# iv17-display-shield.net
KiCad netlist of a schematic drawn in EAGLE
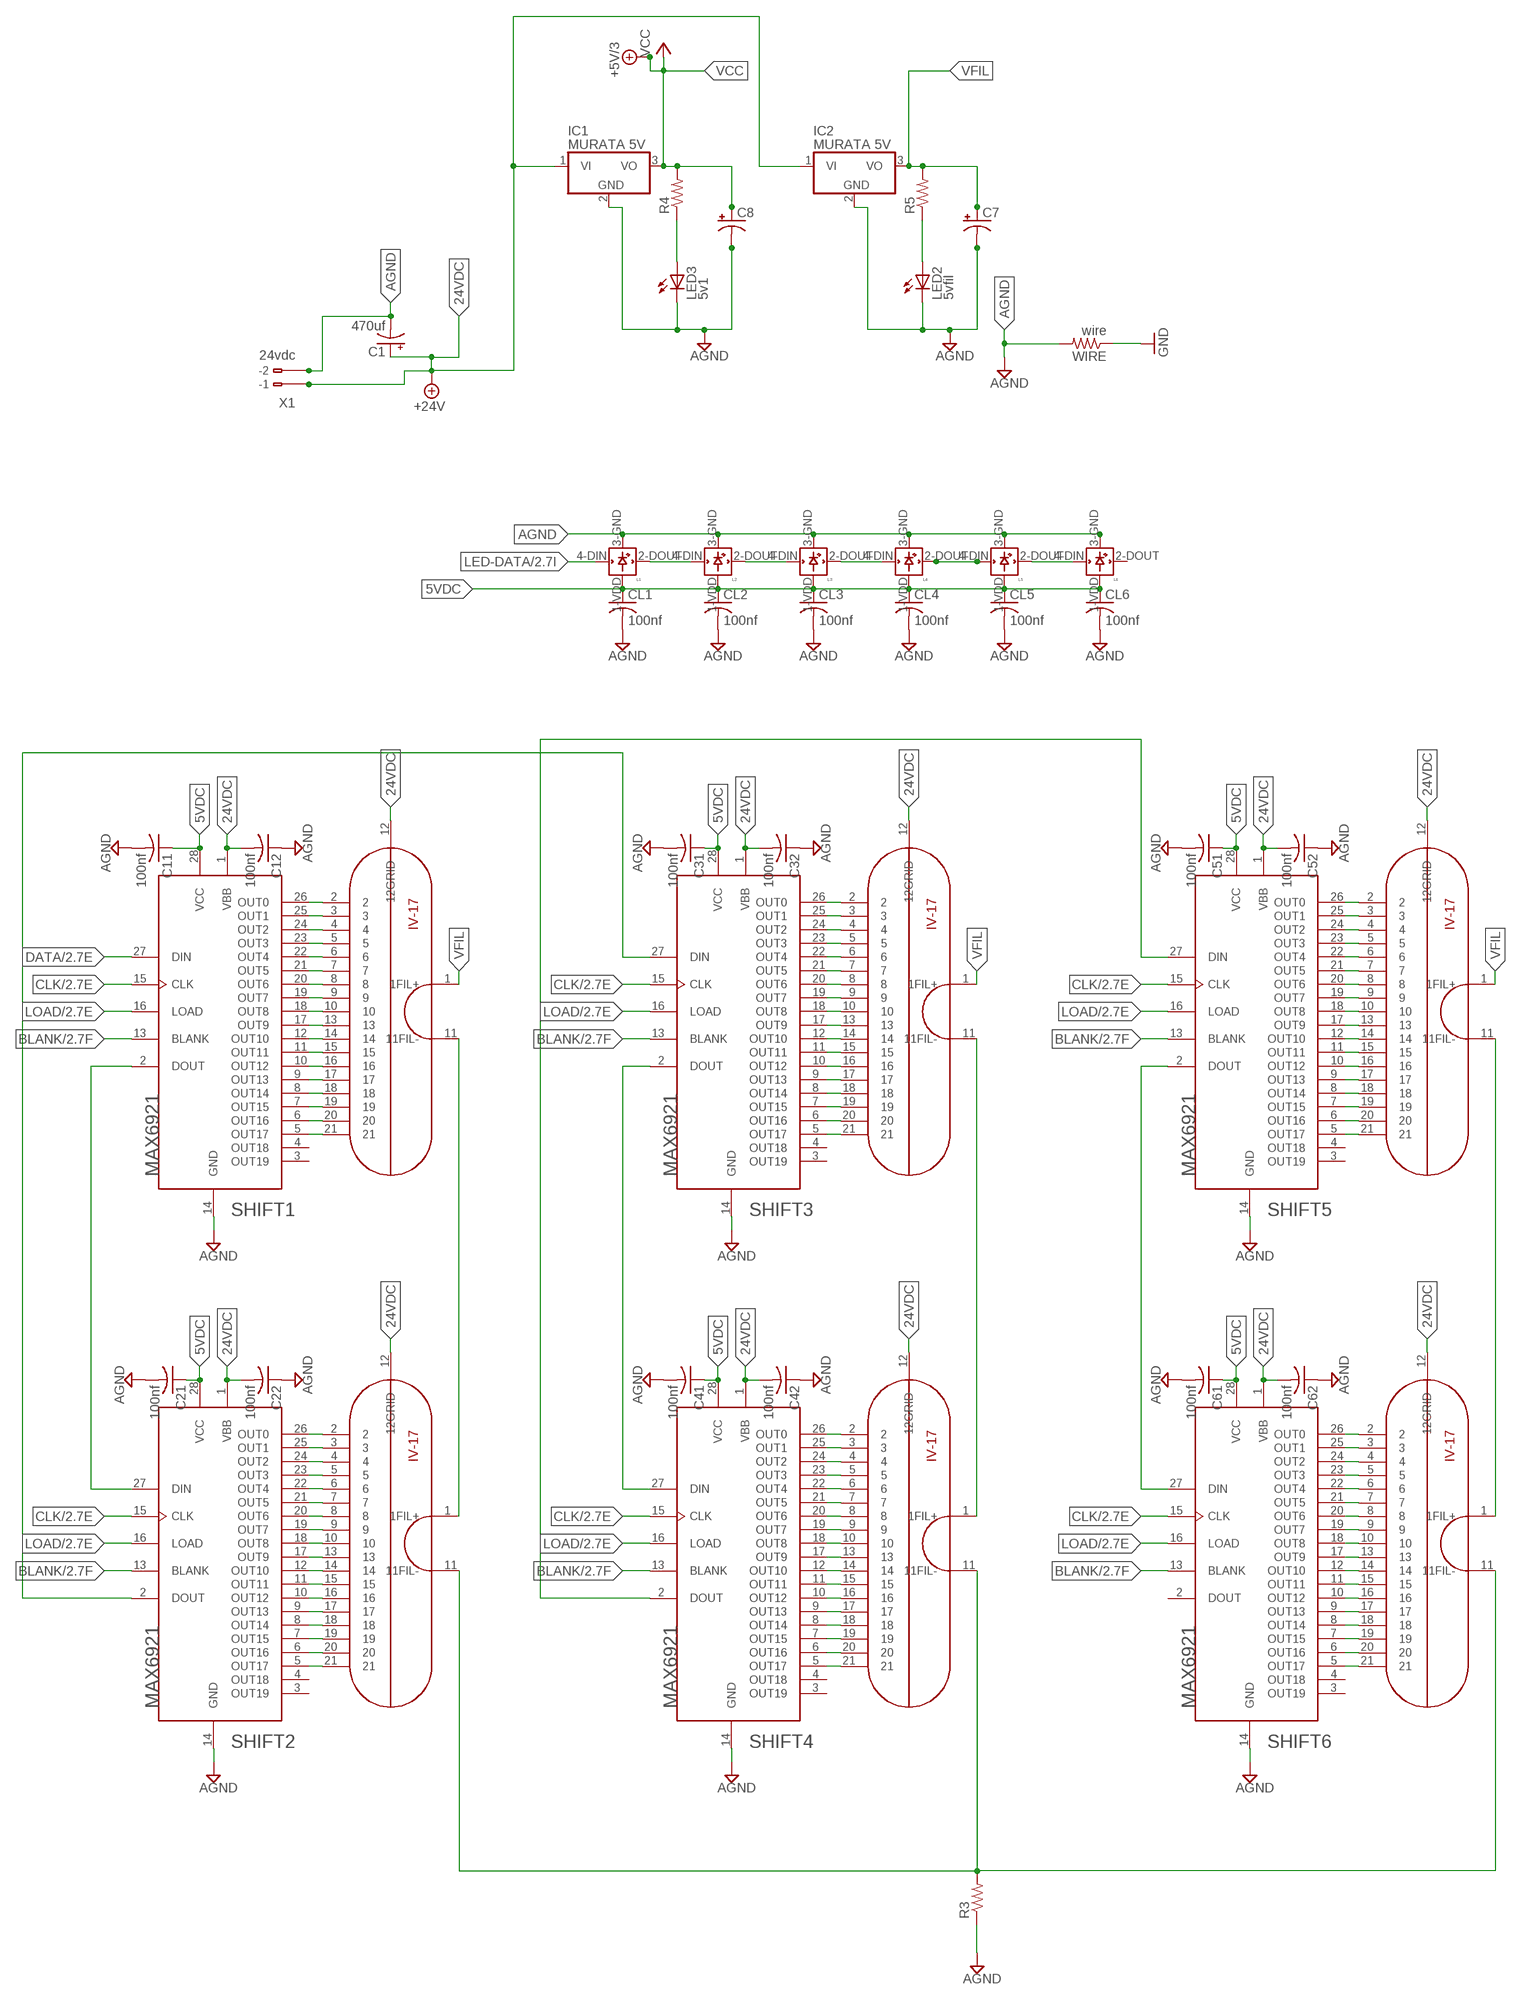
[diagram p0: schematic, sheet 1]
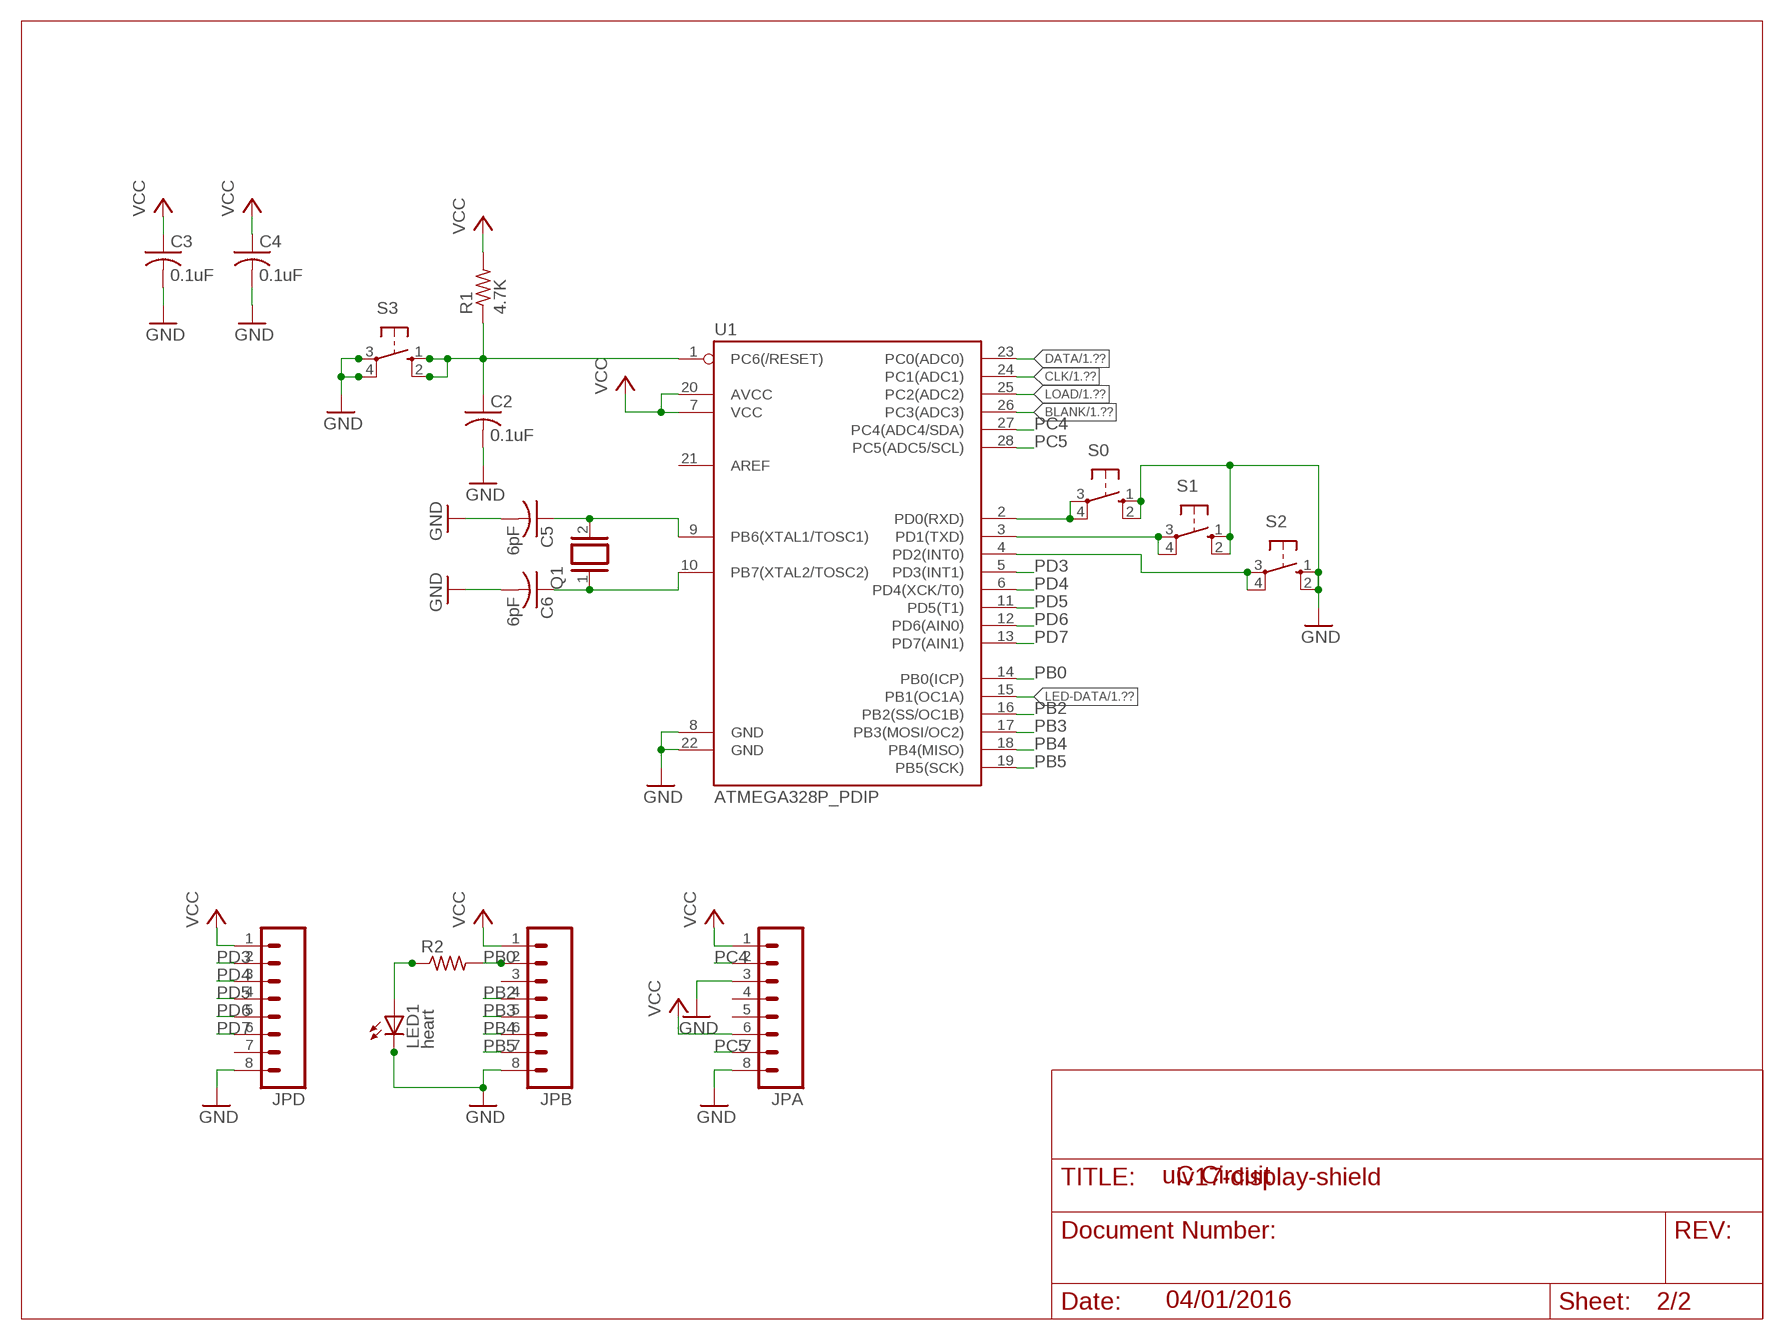
[diagram p1: schematic, sheet 2]

(export (version "E")
  (design (tool "Eeschema 10.0.6"))
  (components
    (comp (ref "C2")
      (value "0.1uF")
      (footprint "eagle-import:C1206")
      (libsource (lib "eagle-import") (part "C-USC1206"))
    )
    (comp (ref "C3")
      (value "0.1uF")
      (footprint "eagle-import:C1206")
      (libsource (lib "eagle-import") (part "C-USC1206"))
    )
    (comp (ref "C4")
      (value "0.1uF")
      (footprint "eagle-import:C1206")
      (libsource (lib "eagle-import") (part "C-USC1206"))
    )
    (comp (ref "C5")
      (value "6pF")
      (footprint "eagle-import:C1206")
      (libsource (lib "eagle-import") (part "C-USC1206"))
    )
    (comp (ref "C6")
      (value "6pF")
      (footprint "eagle-import:C1206")
      (libsource (lib "eagle-import") (part "C-USC1206"))
    )
    (comp (ref "JPA")
      (value "M08")
      (footprint "eagle-import:1X08_ROUND")
      (libsource (lib "eagle-import") (part "M08"))
    )
    (comp (ref "JPB")
      (value "M08")
      (footprint "eagle-import:1X08_ROUND")
      (libsource (lib "eagle-import") (part "M08"))
    )
    (comp (ref "JPD")
      (value "M08")
      (footprint "eagle-import:1X08_ROUND")
      (libsource (lib "eagle-import") (part "M08"))
    )
    (comp (ref "LED1")
      (value "heart")
      (footprint "eagle-import:LED3MM")
      (fields (field (name "MF") "VISHAY SEMICONDUCTOR"))
      (libsource (lib "eagle-import") (part "TLLG4400"))
    )
    (comp (ref "Q1")
      (value "XTAL/S")
      (footprint "eagle-import:QS")
      (libsource (lib "eagle-import") (part "XTAL/S"))
    )
    (comp (ref "R1")
      (value "4.7K")
      (footprint "eagle-import:0309_12")
      (libsource (lib "eagle-import") (part "R-US_0309/12"))
    )
    (comp (ref "R2")
      (value "R-US_M1206")
      (footprint "eagle-import:M1206")
      (libsource (lib "eagle-import") (part "resistor_R-US_M1206"))
    )
    (comp (ref "S0")
      (value "40-XX")
      (footprint "eagle-import:B3F-40XX")
      (fields (field (name "MF") "OMRON COMPONENTS USA") (field (name "MPN") "B3F-4000"))
      (libsource (lib "eagle-import") (part "40-XX"))
    )
    (comp (ref "S1")
      (value "40-XX")
      (footprint "eagle-import:B3F-40XX")
      (fields (field (name "MF") "OMRON COMPONENTS USA") (field (name "MPN") "B3F-4000"))
      (libsource (lib "eagle-import") (part "40-XX"))
    )
    (comp (ref "S2")
      (value "40-XX")
      (footprint "eagle-import:B3F-40XX")
      (fields (field (name "MF") "OMRON COMPONENTS USA") (field (name "MPN") "B3F-4000"))
      (libsource (lib "eagle-import") (part "40-XX"))
    )
    (comp (ref "S3")
      (value "10-XX")
      (footprint "eagle-import:B3F-10XX")
      (fields (field (name "MPN") "B3F-1000"))
      (libsource (lib "eagle-import") (part "10-XX"))
    )
    (comp (ref "U1")
      (value "ATMEGA328P_PDIP")
      (footprint "eagle-import:DIL28-3")
      (libsource (lib "eagle-import") (part "ATMEGA328P_PDIP"))
    )
    (comp (ref "C1")
      (value "470uf")
      (footprint "eagle-import:E5-10,5")
      (libsource (lib "eagle-import") (part "CPOL-USE5-10.5"))
    )
    (comp (ref "C7")
      (value "CPOL-USE5-13")
      (footprint "eagle-import:E5-13")
      (libsource (lib "eagle-import") (part "CPOL-USE5-13"))
    )
    (comp (ref "C8")
      (value "CPOL-USE5-13")
      (footprint "eagle-import:E5-13")
      (libsource (lib "eagle-import") (part "CPOL-USE5-13"))
    )
    (comp (ref "C11")
      (value "100nf")
      (footprint "eagle-import:C1206")
      (libsource (lib "eagle-import") (part "C-USC1206"))
    )
    (comp (ref "C12")
      (value "100nf")
      (footprint "eagle-import:C1206")
      (libsource (lib "eagle-import") (part "C-USC1206"))
    )
    (comp (ref "C21")
      (value "100nf")
      (footprint "eagle-import:C1206")
      (libsource (lib "eagle-import") (part "C-USC1206"))
    )
    (comp (ref "C22")
      (value "100nf")
      (footprint "eagle-import:C1206")
      (libsource (lib "eagle-import") (part "C-USC1206"))
    )
    (comp (ref "C31")
      (value "100nf")
      (footprint "eagle-import:C1206")
      (libsource (lib "eagle-import") (part "C-USC1206"))
    )
    (comp (ref "C32")
      (value "100nf")
      (footprint "eagle-import:C1206")
      (libsource (lib "eagle-import") (part "C-USC1206"))
    )
    (comp (ref "C41")
      (value "100nf")
      (footprint "eagle-import:C1206")
      (libsource (lib "eagle-import") (part "C-USC1206"))
    )
    (comp (ref "C42")
      (value "100nf")
      (footprint "eagle-import:C1206")
      (libsource (lib "eagle-import") (part "C-USC1206"))
    )
    (comp (ref "C51")
      (value "100nf")
      (footprint "eagle-import:C1206")
      (libsource (lib "eagle-import") (part "C-USC1206"))
    )
    (comp (ref "C52")
      (value "100nf")
      (footprint "eagle-import:C1206")
      (libsource (lib "eagle-import") (part "C-USC1206"))
    )
    (comp (ref "C61")
      (value "100nf")
      (footprint "eagle-import:C1206")
      (libsource (lib "eagle-import") (part "C-USC1206"))
    )
    (comp (ref "C62")
      (value "100nf")
      (footprint "eagle-import:C1206")
      (libsource (lib "eagle-import") (part "C-USC1206"))
    )
    (comp (ref "CL1")
      (value "100nf")
      (footprint "eagle-import:C1206")
      (libsource (lib "eagle-import") (part "C-USC1206"))
    )
    (comp (ref "CL2")
      (value "100nf")
      (footprint "eagle-import:C1206")
      (libsource (lib "eagle-import") (part "C-USC1206"))
    )
    (comp (ref "CL3")
      (value "100nf")
      (footprint "eagle-import:C1206")
      (libsource (lib "eagle-import") (part "C-USC1206"))
    )
    (comp (ref "CL4")
      (value "100nf")
      (footprint "eagle-import:C1206")
      (libsource (lib "eagle-import") (part "C-USC1206"))
    )
    (comp (ref "CL5")
      (value "100nf")
      (footprint "eagle-import:C1206")
      (libsource (lib "eagle-import") (part "C-USC1206"))
    )
    (comp (ref "CL6")
      (value "100nf")
      (footprint "eagle-import:C1206")
      (libsource (lib "eagle-import") (part "C-USC1206"))
    )
    (comp (ref "IC1")
      (value "MURATA 5V")
      (footprint "eagle-import:TO220V")
      (libsource (lib "eagle-import") (part "78TV6"))
    )
    (comp (ref "IC2")
      (value "MURATA 5V")
      (footprint "eagle-import:TO220V")
      (libsource (lib "eagle-import") (part "78TV6"))
    )
    (comp (ref "L1")
      (value "WS2812B")
      (footprint "eagle-import:WS2812B")
      (libsource (lib "eagle-import") (part "WS2812B"))
    )
    (comp (ref "L2")
      (value "WS2812B")
      (footprint "eagle-import:WS2812B")
      (libsource (lib "eagle-import") (part "WS2812B"))
    )
    (comp (ref "L3")
      (value "WS2812B")
      (footprint "eagle-import:WS2812B")
      (libsource (lib "eagle-import") (part "WS2812B"))
    )
    (comp (ref "L4")
      (value "WS2812B")
      (footprint "eagle-import:WS2812B")
      (libsource (lib "eagle-import") (part "WS2812B"))
    )
    (comp (ref "L5")
      (value "WS2812B")
      (footprint "eagle-import:WS2812B")
      (libsource (lib "eagle-import") (part "WS2812B"))
    )
    (comp (ref "L6")
      (value "WS2812B")
      (footprint "eagle-import:WS2812B")
      (libsource (lib "eagle-import") (part "WS2812B"))
    )
    (comp (ref "LED2")
      (value "5vfil")
      (footprint "eagle-import:LED3MM")
      (fields (field (name "MF") "VISHAY SEMICONDUCTOR"))
      (libsource (lib "eagle-import") (part "TLLR4400"))
    )
    (comp (ref "LED3")
      (value "5v1")
      (footprint "eagle-import:LED3MM")
      (fields (field (name "MF") "VISHAY SEMICONDUCTOR"))
      (libsource (lib "eagle-import") (part "TLLR4400"))
    )
    (comp (ref "R3")
      (value "R-US_0309/12")
      (footprint "eagle-import:0309_12")
      (libsource (lib "eagle-import") (part "R-US_0309/12"))
    )
    (comp (ref "R4")
      (value "R-US_M1206")
      (footprint "eagle-import:M1206")
      (libsource (lib "eagle-import") (part "resistor_R-US_M1206"))
    )
    (comp (ref "R5")
      (value "R-US_M1206")
      (footprint "eagle-import:M1206")
      (libsource (lib "eagle-import") (part "resistor_R-US_M1206"))
    )
    (comp (ref "SHIFT1")
      (value "MAX6921")
      (footprint "eagle-import:SOIC-28W")
      (libsource (lib "eagle-import") (part "MAX6921"))
    )
    (comp (ref "SHIFT2")
      (value "MAX6921")
      (footprint "eagle-import:SOIC-28W")
      (libsource (lib "eagle-import") (part "MAX6921"))
    )
    (comp (ref "SHIFT3")
      (value "MAX6921")
      (footprint "eagle-import:SOIC-28W")
      (libsource (lib "eagle-import") (part "MAX6921"))
    )
    (comp (ref "SHIFT4")
      (value "MAX6921")
      (footprint "eagle-import:SOIC-28W")
      (libsource (lib "eagle-import") (part "MAX6921"))
    )
    (comp (ref "SHIFT5")
      (value "MAX6921")
      (footprint "eagle-import:SOIC-28W")
      (libsource (lib "eagle-import") (part "MAX6921"))
    )
    (comp (ref "SHIFT6")
      (value "MAX6921")
      (footprint "eagle-import:SOIC-28W")
      (libsource (lib "eagle-import") (part "MAX6921"))
    )
    (comp (ref "TUBE1")
      (value "IV17")
      (footprint "eagle-import:NIXIE-22")
      (libsource (lib "eagle-import") (part "IV17"))
    )
    (comp (ref "TUBE2")
      (value "IV17")
      (footprint "eagle-import:NIXIE-22")
      (libsource (lib "eagle-import") (part "IV17"))
    )
    (comp (ref "TUBE3")
      (value "IV17")
      (footprint "eagle-import:NIXIE-22")
      (libsource (lib "eagle-import") (part "IV17"))
    )
    (comp (ref "TUBE4")
      (value "IV17")
      (footprint "eagle-import:NIXIE-22")
      (libsource (lib "eagle-import") (part "IV17"))
    )
    (comp (ref "TUBE5")
      (value "IV17")
      (footprint "eagle-import:NIXIE-22")
      (libsource (lib "eagle-import") (part "IV17"))
    )
    (comp (ref "TUBE6")
      (value "IV17")
      (footprint "eagle-import:NIXIE-22")
      (libsource (lib "eagle-import") (part "IV17"))
    )
    (comp (ref "WIRE")
      (value "wire")
      (footprint "eagle-import:0309_12")
      (libsource (lib "eagle-import") (part "R-US_0309/12"))
    )
    (comp (ref "X1")
      (value "24vdc")
      (footprint "eagle-import:233-102")
      (fields (field (name "MPN") "233-102"))
      (libsource (lib "eagle-import") (part "233-102"))
    )
  )
  (nets
    (net (code "1") (name "5VDC") (class "Default")
      (node (ref "C11") (pin "1") (pinfunction "1_1") (pintype "passive"))
      (node (ref "C21") (pin "1") (pinfunction "1_1") (pintype "passive"))
      (node (ref "C31") (pin "1") (pinfunction "1_1") (pintype "passive"))
      (node (ref "C41") (pin "1") (pinfunction "1_1") (pintype "passive"))
      (node (ref "C51") (pin "1") (pinfunction "1_1") (pintype "passive"))
      (node (ref "C61") (pin "1") (pinfunction "1_1") (pintype "passive"))
      (node (ref "CL1") (pin "1") (pinfunction "1_1") (pintype "passive"))
      (node (ref "CL2") (pin "1") (pinfunction "1_1") (pintype "passive"))
      (node (ref "CL3") (pin "1") (pinfunction "1_1") (pintype "passive"))
      (node (ref "CL4") (pin "1") (pinfunction "1_1") (pintype "passive"))
      (node (ref "CL5") (pin "1") (pinfunction "1_1") (pintype "passive"))
      (node (ref "CL6") (pin "1") (pinfunction "1_1") (pintype "passive"))
      (node (ref "L1") (pin "1-VDD") (pinfunction "VDD_1-VDD") (pintype "bidirectional"))
      (node (ref "L2") (pin "1-VDD") (pinfunction "VDD_1-VDD") (pintype "bidirectional"))
      (node (ref "L3") (pin "1-VDD") (pinfunction "VDD_1-VDD") (pintype "bidirectional"))
      (node (ref "L4") (pin "1-VDD") (pinfunction "VDD_1-VDD") (pintype "bidirectional"))
      (node (ref "L5") (pin "1-VDD") (pinfunction "VDD_1-VDD") (pintype "bidirectional"))
      (node (ref "L6") (pin "1-VDD") (pinfunction "VDD_1-VDD") (pintype "bidirectional"))
      (node (ref "SHIFT1") (pin "28") (pinfunction "VCC_28") (pintype "power_in"))
      (node (ref "SHIFT2") (pin "28") (pinfunction "VCC_28") (pintype "power_in"))
      (node (ref "SHIFT3") (pin "28") (pinfunction "VCC_28") (pintype "power_in"))
      (node (ref "SHIFT4") (pin "28") (pinfunction "VCC_28") (pintype "power_in"))
      (node (ref "SHIFT5") (pin "28") (pinfunction "VCC_28") (pintype "power_in"))
      (node (ref "SHIFT6") (pin "28") (pinfunction "VCC_28") (pintype "power_in"))
    )
    (net (code "2") (name "24VDC") (class "Default")
      (node (ref "C1") (pin "+") (pinfunction "+_+") (pintype "passive"))
      (node (ref "C12") (pin "2") (pinfunction "2_2") (pintype "passive"))
      (node (ref "C22") (pin "2") (pinfunction "2_2") (pintype "passive"))
      (node (ref "C32") (pin "2") (pinfunction "2_2") (pintype "passive"))
      (node (ref "C42") (pin "2") (pinfunction "2_2") (pintype "passive"))
      (node (ref "C52") (pin "2") (pinfunction "2_2") (pintype "passive"))
      (node (ref "C62") (pin "2") (pinfunction "2_2") (pintype "passive"))
      (node (ref "IC1") (pin "1") (pinfunction "VI_1") (pintype "input"))
      (node (ref "IC2") (pin "1") (pinfunction "VI_1") (pintype "input"))
      (node (ref "SHIFT1") (pin "1") (pinfunction "VBB_1") (pintype "power_in"))
      (node (ref "SHIFT2") (pin "1") (pinfunction "VBB_1") (pintype "power_in"))
      (node (ref "SHIFT3") (pin "1") (pinfunction "VBB_1") (pintype "power_in"))
      (node (ref "SHIFT4") (pin "1") (pinfunction "VBB_1") (pintype "power_in"))
      (node (ref "SHIFT5") (pin "1") (pinfunction "VBB_1") (pintype "power_in"))
      (node (ref "SHIFT6") (pin "1") (pinfunction "VBB_1") (pintype "power_in"))
      (node (ref "TUBE1") (pin "12") (pinfunction "12GRID_12") (pintype "bidirectional"))
      (node (ref "TUBE2") (pin "12") (pinfunction "12GRID_12") (pintype "bidirectional"))
      (node (ref "TUBE3") (pin "12") (pinfunction "12GRID_12") (pintype "bidirectional"))
      (node (ref "TUBE4") (pin "12") (pinfunction "12GRID_12") (pintype "bidirectional"))
      (node (ref "TUBE5") (pin "12") (pinfunction "12GRID_12") (pintype "bidirectional"))
      (node (ref "TUBE6") (pin "12") (pinfunction "12GRID_12") (pintype "bidirectional"))
      (node (ref "X1") (pin "B1") (pinfunction "B-1_B1") (pintype "passive"))
    )
    (net (code "3") (name "AGND") (class "Default")
      (node (ref "C1") (pin "-") (pinfunction "-_-") (pintype "passive"))
      (node (ref "C11") (pin "2") (pinfunction "2_2") (pintype "passive"))
      (node (ref "C12") (pin "1") (pinfunction "1_1") (pintype "passive"))
      (node (ref "C21") (pin "2") (pinfunction "2_2") (pintype "passive"))
      (node (ref "C22") (pin "1") (pinfunction "1_1") (pintype "passive"))
      (node (ref "C31") (pin "2") (pinfunction "2_2") (pintype "passive"))
      (node (ref "C32") (pin "1") (pinfunction "1_1") (pintype "passive"))
      (node (ref "C41") (pin "2") (pinfunction "2_2") (pintype "passive"))
      (node (ref "C42") (pin "1") (pinfunction "1_1") (pintype "passive"))
      (node (ref "C51") (pin "2") (pinfunction "2_2") (pintype "passive"))
      (node (ref "C52") (pin "1") (pinfunction "1_1") (pintype "passive"))
      (node (ref "C61") (pin "2") (pinfunction "2_2") (pintype "passive"))
      (node (ref "C62") (pin "1") (pinfunction "1_1") (pintype "passive"))
      (node (ref "C7") (pin "-") (pinfunction "-_-") (pintype "passive"))
      (node (ref "C8") (pin "-") (pinfunction "-_-") (pintype "passive"))
      (node (ref "CL1") (pin "2") (pinfunction "2_2") (pintype "passive"))
      (node (ref "CL2") (pin "2") (pinfunction "2_2") (pintype "passive"))
      (node (ref "CL3") (pin "2") (pinfunction "2_2") (pintype "passive"))
      (node (ref "CL4") (pin "2") (pinfunction "2_2") (pintype "passive"))
      (node (ref "CL5") (pin "2") (pinfunction "2_2") (pintype "passive"))
      (node (ref "CL6") (pin "2") (pinfunction "2_2") (pintype "passive"))
      (node (ref "IC1") (pin "2") (pinfunction "GND_2") (pintype "passive"))
      (node (ref "IC2") (pin "2") (pinfunction "GND_2") (pintype "passive"))
      (node (ref "L1") (pin "3-GND") (pinfunction "GND_3-GND") (pintype "bidirectional"))
      (node (ref "L2") (pin "3-GND") (pinfunction "GND_3-GND") (pintype "bidirectional"))
      (node (ref "L3") (pin "3-GND") (pinfunction "GND_3-GND") (pintype "bidirectional"))
      (node (ref "L4") (pin "3-GND") (pinfunction "GND_3-GND") (pintype "bidirectional"))
      (node (ref "L5") (pin "3-GND") (pinfunction "GND_3-GND") (pintype "bidirectional"))
      (node (ref "L6") (pin "3-GND") (pinfunction "GND_3-GND") (pintype "bidirectional"))
      (node (ref "LED2") (pin "K") (pinfunction "C_K") (pintype "passive"))
      (node (ref "LED3") (pin "K") (pinfunction "C_K") (pintype "passive"))
      (node (ref "R3") (pin "1") (pinfunction "1_1") (pintype "passive"))
      (node (ref "SHIFT1") (pin "14") (pinfunction "GND_14") (pintype "power_in"))
      (node (ref "SHIFT2") (pin "14") (pinfunction "GND_14") (pintype "power_in"))
      (node (ref "SHIFT3") (pin "14") (pinfunction "GND_14") (pintype "power_in"))
      (node (ref "SHIFT4") (pin "14") (pinfunction "GND_14") (pintype "power_in"))
      (node (ref "SHIFT5") (pin "14") (pinfunction "GND_14") (pintype "power_in"))
      (node (ref "SHIFT6") (pin "14") (pinfunction "GND_14") (pintype "power_in"))
      (node (ref "WIRE") (pin "2") (pinfunction "2_2") (pintype "passive"))
      (node (ref "X1") (pin "B2") (pinfunction "B-2_B2") (pintype "passive"))
    )
    (net (code "4") (name "BLANK") (class "Default")
      (node (ref "SHIFT1") (pin "13") (pinfunction "BLANK_13") (pintype "input"))
      (node (ref "SHIFT2") (pin "13") (pinfunction "BLANK_13") (pintype "input"))
      (node (ref "SHIFT3") (pin "13") (pinfunction "BLANK_13") (pintype "input"))
      (node (ref "SHIFT4") (pin "13") (pinfunction "BLANK_13") (pintype "input"))
      (node (ref "SHIFT5") (pin "13") (pinfunction "BLANK_13") (pintype "input"))
      (node (ref "SHIFT6") (pin "13") (pinfunction "BLANK_13") (pintype "input"))
      (node (ref "U1") (pin "26") (pinfunction "PC3(ADC3)_26") (pintype "bidirectional"))
    )
    (net (code "5") (name "CLK") (class "Default")
      (node (ref "SHIFT1") (pin "15") (pinfunction "CLK_15") (pintype "input"))
      (node (ref "SHIFT2") (pin "15") (pinfunction "CLK_15") (pintype "input"))
      (node (ref "SHIFT3") (pin "15") (pinfunction "CLK_15") (pintype "input"))
      (node (ref "SHIFT4") (pin "15") (pinfunction "CLK_15") (pintype "input"))
      (node (ref "SHIFT5") (pin "15") (pinfunction "CLK_15") (pintype "input"))
      (node (ref "SHIFT6") (pin "15") (pinfunction "CLK_15") (pintype "input"))
      (node (ref "U1") (pin "24") (pinfunction "PC1(ADC1)_24") (pintype "bidirectional"))
    )
    (net (code "6") (name "DATA") (class "Default")
      (node (ref "SHIFT1") (pin "27") (pinfunction "DIN_27") (pintype "input"))
      (node (ref "U1") (pin "23") (pinfunction "PC0(ADC0)_23") (pintype "bidirectional"))
    )
    (net (code "7") (name "GND") (class "Default")
      (node (ref "C2") (pin "2") (pinfunction "2_2") (pintype "passive"))
      (node (ref "C3") (pin "2") (pinfunction "2_2") (pintype "passive"))
      (node (ref "C4") (pin "2") (pinfunction "2_2") (pintype "passive"))
      (node (ref "C5") (pin "2") (pinfunction "2_2") (pintype "passive"))
      (node (ref "C6") (pin "2") (pinfunction "2_2") (pintype "passive"))
      (node (ref "JPA") (pin "3") (pinfunction "3_3") (pintype "passive"))
      (node (ref "JPA") (pin "8") (pinfunction "8_8") (pintype "passive"))
      (node (ref "JPB") (pin "8") (pinfunction "8_8") (pintype "passive"))
      (node (ref "JPD") (pin "8") (pinfunction "8_8") (pintype "passive"))
      (node (ref "LED1") (pin "K") (pinfunction "C_K") (pintype "passive"))
      (node (ref "S0") (pin "1") (pinfunction "S_1") (pintype "passive"))
      (node (ref "S0") (pin "2") (pinfunction "S1_2") (pintype "passive"))
      (node (ref "S1") (pin "1") (pinfunction "S_1") (pintype "passive"))
      (node (ref "S1") (pin "2") (pinfunction "S1_2") (pintype "passive"))
      (node (ref "S2") (pin "1") (pinfunction "S_1") (pintype "passive"))
      (node (ref "S2") (pin "2") (pinfunction "S1_2") (pintype "passive"))
      (node (ref "S3") (pin "3") (pinfunction "P_3") (pintype "passive"))
      (node (ref "S3") (pin "4") (pinfunction "P1_4") (pintype "passive"))
      (node (ref "U1") (pin "22") (pinfunction "GND_22") (pintype "bidirectional"))
      (node (ref "U1") (pin "8") (pinfunction "GND_8") (pintype "bidirectional"))
      (node (ref "WIRE") (pin "1") (pinfunction "1_1") (pintype "passive"))
    )
    (net (code "8") (name "LED-DATA") (class "Default")
      (node (ref "L1") (pin "4-DIN") (pinfunction "DIN_4-DIN") (pintype "input"))
      (node (ref "U1") (pin "15") (pinfunction "PB1(OC1A)_15") (pintype "bidirectional"))
    )
    (net (code "9") (name "LOAD") (class "Default")
      (node (ref "SHIFT1") (pin "16") (pinfunction "LOAD_16") (pintype "input"))
      (node (ref "SHIFT2") (pin "16") (pinfunction "LOAD_16") (pintype "input"))
      (node (ref "SHIFT3") (pin "16") (pinfunction "LOAD_16") (pintype "input"))
      (node (ref "SHIFT4") (pin "16") (pinfunction "LOAD_16") (pintype "input"))
      (node (ref "SHIFT5") (pin "16") (pinfunction "LOAD_16") (pintype "input"))
      (node (ref "SHIFT6") (pin "16") (pinfunction "LOAD_16") (pintype "input"))
      (node (ref "U1") (pin "25") (pinfunction "PC2(ADC2)_25") (pintype "bidirectional"))
    )
    (net (code "10") (name "Net-(L1-DOUT)") (class "Default")
      (node (ref "L1") (pin "2-DOUT") (pinfunction "DOUT_2-DOUT") (pintype "output"))
      (node (ref "L2") (pin "4-DIN") (pinfunction "DIN_4-DIN") (pintype "input"))
    )
    (net (code "11") (name "Net-(L2-DOUT)") (class "Default")
      (node (ref "L2") (pin "2-DOUT") (pinfunction "DOUT_2-DOUT") (pintype "output"))
      (node (ref "L3") (pin "4-DIN") (pinfunction "DIN_4-DIN") (pintype "input"))
    )
    (net (code "12") (name "Net-(L3-DOUT)") (class "Default")
      (node (ref "L3") (pin "2-DOUT") (pinfunction "DOUT_2-DOUT") (pintype "output"))
      (node (ref "L4") (pin "4-DIN") (pinfunction "DIN_4-DIN") (pintype "input"))
    )
    (net (code "13") (name "Net-(L4-DOUT)") (class "Default")
      (node (ref "L4") (pin "2-DOUT") (pinfunction "DOUT_2-DOUT") (pintype "output"))
      (node (ref "L5") (pin "4-DIN") (pinfunction "DIN_4-DIN") (pintype "input"))
    )
    (net (code "14") (name "Net-(L5-DOUT)") (class "Default")
      (node (ref "L5") (pin "2-DOUT") (pinfunction "DOUT_2-DOUT") (pintype "output"))
      (node (ref "L6") (pin "4-DIN") (pinfunction "DIN_4-DIN") (pintype "input"))
    )
    (net (code "15") (name "Net-(LED1-PadA)") (class "Default")
      (node (ref "LED1") (pin "A") (pinfunction "A_A") (pintype "passive"))
      (node (ref "R2") (pin "1") (pinfunction "1_1") (pintype "passive"))
    )
    (net (code "16") (name "Net-(LED2-PadA)") (class "Default")
      (node (ref "LED2") (pin "A") (pinfunction "A_A") (pintype "passive"))
      (node (ref "R5") (pin "1") (pinfunction "1_1") (pintype "passive"))
    )
    (net (code "17") (name "Net-(LED3-PadA)") (class "Default")
      (node (ref "LED3") (pin "A") (pinfunction "A_A") (pintype "passive"))
      (node (ref "R4") (pin "1") (pinfunction "1_1") (pintype "passive"))
    )
    (net (code "18") (name "Net-(S0-P)") (class "Default")
      (node (ref "S0") (pin "3") (pinfunction "P_3") (pintype "passive"))
      (node (ref "S0") (pin "4") (pinfunction "P1_4") (pintype "passive"))
      (node (ref "U1") (pin "2") (pinfunction "PD0(RXD)_2") (pintype "bidirectional"))
    )
    (net (code "19") (name "Net-(S1-P)") (class "Default")
      (node (ref "S1") (pin "3") (pinfunction "P_3") (pintype "passive"))
      (node (ref "S1") (pin "4") (pinfunction "P1_4") (pintype "passive"))
      (node (ref "U1") (pin "3") (pinfunction "PD1(TXD)_3") (pintype "bidirectional"))
    )
    (net (code "20") (name "Net-(S2-P)") (class "Default")
      (node (ref "S2") (pin "3") (pinfunction "P_3") (pintype "passive"))
      (node (ref "S2") (pin "4") (pinfunction "P1_4") (pintype "passive"))
      (node (ref "U1") (pin "4") (pinfunction "PD2(INT0)_4") (pintype "bidirectional"))
    )
    (net (code "21") (name "Net-(S3-S)") (class "Default")
      (node (ref "C2") (pin "1") (pinfunction "1_1") (pintype "passive"))
      (node (ref "R1") (pin "1") (pinfunction "1_1") (pintype "passive"))
      (node (ref "S3") (pin "1") (pinfunction "S_1") (pintype "passive"))
      (node (ref "S3") (pin "2") (pinfunction "S1_2") (pintype "passive"))
      (node (ref "U1") (pin "1") (pinfunction "PC6(/RESET)_1") (pintype "bidirectional"))
    )
    (net (code "22") (name "Net-(SHIFT1-DOUT)") (class "Default")
      (node (ref "SHIFT1") (pin "2") (pinfunction "DOUT_2") (pintype "output"))
      (node (ref "SHIFT2") (pin "27") (pinfunction "DIN_27") (pintype "input"))
    )
    (net (code "23") (name "Net-(SHIFT1-OUT0)") (class "Default")
      (node (ref "SHIFT1") (pin "26") (pinfunction "OUT0_26") (pintype "output"))
      (node (ref "TUBE1") (pin "2") (pinfunction "2_2") (pintype "bidirectional"))
    )
    (net (code "24") (name "Net-(SHIFT1-OUT1)") (class "Default")
      (node (ref "SHIFT1") (pin "25") (pinfunction "OUT1_25") (pintype "output"))
      (node (ref "TUBE1") (pin "3") (pinfunction "3_3") (pintype "bidirectional"))
    )
    (net (code "25") (name "Net-(SHIFT1-OUT2)") (class "Default")
      (node (ref "SHIFT1") (pin "24") (pinfunction "OUT2_24") (pintype "output"))
      (node (ref "TUBE1") (pin "4") (pinfunction "4_4") (pintype "bidirectional"))
    )
    (net (code "26") (name "Net-(SHIFT1-OUT3)") (class "Default")
      (node (ref "SHIFT1") (pin "23") (pinfunction "OUT3_23") (pintype "output"))
      (node (ref "TUBE1") (pin "5") (pinfunction "5_5") (pintype "bidirectional"))
    )
    (net (code "27") (name "Net-(SHIFT1-OUT4)") (class "Default")
      (node (ref "SHIFT1") (pin "22") (pinfunction "OUT4_22") (pintype "output"))
      (node (ref "TUBE1") (pin "6") (pinfunction "6_6") (pintype "bidirectional"))
    )
    (net (code "28") (name "Net-(SHIFT1-OUT5)") (class "Default")
      (node (ref "SHIFT1") (pin "21") (pinfunction "OUT5_21") (pintype "output"))
      (node (ref "TUBE1") (pin "7") (pinfunction "7_7") (pintype "bidirectional"))
    )
    (net (code "29") (name "Net-(SHIFT1-OUT6)") (class "Default")
      (node (ref "SHIFT1") (pin "20") (pinfunction "OUT6_20") (pintype "output"))
      (node (ref "TUBE1") (pin "8") (pinfunction "8_8") (pintype "bidirectional"))
    )
    (net (code "30") (name "Net-(SHIFT1-OUT7)") (class "Default")
      (node (ref "SHIFT1") (pin "19") (pinfunction "OUT7_19") (pintype "output"))
      (node (ref "TUBE1") (pin "9") (pinfunction "9_9") (pintype "bidirectional"))
    )
    (net (code "31") (name "Net-(SHIFT1-OUT8)") (class "Default")
      (node (ref "SHIFT1") (pin "18") (pinfunction "OUT8_18") (pintype "output"))
      (node (ref "TUBE1") (pin "10") (pinfunction "10_10") (pintype "bidirectional"))
    )
    (net (code "32") (name "Net-(SHIFT1-OUT9)") (class "Default")
      (node (ref "SHIFT1") (pin "17") (pinfunction "OUT9_17") (pintype "output"))
      (node (ref "TUBE1") (pin "13") (pinfunction "13_13") (pintype "bidirectional"))
    )
    (net (code "33") (name "Net-(SHIFT1-OUT10)") (class "Default")
      (node (ref "SHIFT1") (pin "12") (pinfunction "OUT10_12") (pintype "output"))
      (node (ref "TUBE1") (pin "14") (pinfunction "14_14") (pintype "bidirectional"))
    )
    (net (code "34") (name "Net-(SHIFT1-OUT11)") (class "Default")
      (node (ref "SHIFT1") (pin "11") (pinfunction "OUT11_11") (pintype "output"))
      (node (ref "TUBE1") (pin "15") (pinfunction "15_15") (pintype "bidirectional"))
    )
    (net (code "35") (name "Net-(SHIFT1-OUT12)") (class "Default")
      (node (ref "SHIFT1") (pin "10") (pinfunction "OUT12_10") (pintype "output"))
      (node (ref "TUBE1") (pin "16") (pinfunction "16_16") (pintype "bidirectional"))
    )
    (net (code "36") (name "Net-(SHIFT1-OUT13)") (class "Default")
      (node (ref "SHIFT1") (pin "9") (pinfunction "OUT13_9") (pintype "output"))
      (node (ref "TUBE1") (pin "17") (pinfunction "17_17") (pintype "bidirectional"))
    )
    (net (code "37") (name "Net-(SHIFT1-OUT14)") (class "Default")
      (node (ref "SHIFT1") (pin "8") (pinfunction "OUT14_8") (pintype "output"))
      (node (ref "TUBE1") (pin "18") (pinfunction "18_18") (pintype "bidirectional"))
    )
    (net (code "38") (name "Net-(SHIFT1-OUT15)") (class "Default")
      (node (ref "SHIFT1") (pin "7") (pinfunction "OUT15_7") (pintype "output"))
      (node (ref "TUBE1") (pin "19") (pinfunction "19_19") (pintype "bidirectional"))
    )
    (net (code "39") (name "Net-(SHIFT1-OUT16)") (class "Default")
      (node (ref "SHIFT1") (pin "6") (pinfunction "OUT16_6") (pintype "output"))
      (node (ref "TUBE1") (pin "20") (pinfunction "20_20") (pintype "bidirectional"))
    )
    (net (code "40") (name "Net-(SHIFT1-OUT17)") (class "Default")
      (node (ref "SHIFT1") (pin "5") (pinfunction "OUT17_5") (pintype "output"))
      (node (ref "TUBE1") (pin "21") (pinfunction "21_21") (pintype "bidirectional"))
    )
    (net (code "41") (name "Net-(SHIFT2-DOUT)") (class "Default")
      (node (ref "SHIFT2") (pin "2") (pinfunction "DOUT_2") (pintype "output"))
      (node (ref "SHIFT3") (pin "27") (pinfunction "DIN_27") (pintype "input"))
    )
    (net (code "42") (name "Net-(SHIFT2-OUT0)") (class "Default")
      (node (ref "SHIFT2") (pin "26") (pinfunction "OUT0_26") (pintype "output"))
      (node (ref "TUBE2") (pin "2") (pinfunction "2_2") (pintype "bidirectional"))
    )
    (net (code "43") (name "Net-(SHIFT2-OUT1)") (class "Default")
      (node (ref "SHIFT2") (pin "25") (pinfunction "OUT1_25") (pintype "output"))
      (node (ref "TUBE2") (pin "3") (pinfunction "3_3") (pintype "bidirectional"))
    )
    (net (code "44") (name "Net-(SHIFT2-OUT2)") (class "Default")
      (node (ref "SHIFT2") (pin "24") (pinfunction "OUT2_24") (pintype "output"))
      (node (ref "TUBE2") (pin "4") (pinfunction "4_4") (pintype "bidirectional"))
    )
    (net (code "45") (name "Net-(SHIFT2-OUT3)") (class "Default")
      (node (ref "SHIFT2") (pin "23") (pinfunction "OUT3_23") (pintype "output"))
      (node (ref "TUBE2") (pin "5") (pinfunction "5_5") (pintype "bidirectional"))
    )
    (net (code "46") (name "Net-(SHIFT2-OUT4)") (class "Default")
      (node (ref "SHIFT2") (pin "22") (pinfunction "OUT4_22") (pintype "output"))
      (node (ref "TUBE2") (pin "6") (pinfunction "6_6") (pintype "bidirectional"))
    )
    (net (code "47") (name "Net-(SHIFT2-OUT5)") (class "Default")
      (node (ref "SHIFT2") (pin "21") (pinfunction "OUT5_21") (pintype "output"))
      (node (ref "TUBE2") (pin "7") (pinfunction "7_7") (pintype "bidirectional"))
    )
    (net (code "48") (name "Net-(SHIFT2-OUT6)") (class "Default")
      (node (ref "SHIFT2") (pin "20") (pinfunction "OUT6_20") (pintype "output"))
      (node (ref "TUBE2") (pin "8") (pinfunction "8_8") (pintype "bidirectional"))
    )
    (net (code "49") (name "Net-(SHIFT2-OUT7)") (class "Default")
      (node (ref "SHIFT2") (pin "19") (pinfunction "OUT7_19") (pintype "output"))
      (node (ref "TUBE2") (pin "9") (pinfunction "9_9") (pintype "bidirectional"))
    )
    (net (code "50") (name "Net-(SHIFT2-OUT8)") (class "Default")
      (node (ref "SHIFT2") (pin "18") (pinfunction "OUT8_18") (pintype "output"))
      (node (ref "TUBE2") (pin "10") (pinfunction "10_10") (pintype "bidirectional"))
    )
    (net (code "51") (name "Net-(SHIFT2-OUT9)") (class "Default")
      (node (ref "SHIFT2") (pin "17") (pinfunction "OUT9_17") (pintype "output"))
      (node (ref "TUBE2") (pin "13") (pinfunction "13_13") (pintype "bidirectional"))
    )
    (net (code "52") (name "Net-(SHIFT2-OUT10)") (class "Default")
      (node (ref "SHIFT2") (pin "12") (pinfunction "OUT10_12") (pintype "output"))
      (node (ref "TUBE2") (pin "14") (pinfunction "14_14") (pintype "bidirectional"))
    )
    (net (code "53") (name "Net-(SHIFT2-OUT11)") (class "Default")
      (node (ref "SHIFT2") (pin "11") (pinfunction "OUT11_11") (pintype "output"))
      (node (ref "TUBE2") (pin "15") (pinfunction "15_15") (pintype "bidirectional"))
    )
    (net (code "54") (name "Net-(SHIFT2-OUT12)") (class "Default")
      (node (ref "SHIFT2") (pin "10") (pinfunction "OUT12_10") (pintype "output"))
      (node (ref "TUBE2") (pin "16") (pinfunction "16_16") (pintype "bidirectional"))
    )
    (net (code "55") (name "Net-(SHIFT2-OUT13)") (class "Default")
      (node (ref "SHIFT2") (pin "9") (pinfunction "OUT13_9") (pintype "output"))
      (node (ref "TUBE2") (pin "17") (pinfunction "17_17") (pintype "bidirectional"))
    )
    (net (code "56") (name "Net-(SHIFT2-OUT14)") (class "Default")
      (node (ref "SHIFT2") (pin "8") (pinfunction "OUT14_8") (pintype "output"))
      (node (ref "TUBE2") (pin "18") (pinfunction "18_18") (pintype "bidirectional"))
    )
    (net (code "57") (name "Net-(SHIFT2-OUT15)") (class "Default")
      (node (ref "SHIFT2") (pin "7") (pinfunction "OUT15_7") (pintype "output"))
      (node (ref "TUBE2") (pin "19") (pinfunction "19_19") (pintype "bidirectional"))
    )
    (net (code "58") (name "Net-(SHIFT2-OUT16)") (class "Default")
      (node (ref "SHIFT2") (pin "6") (pinfunction "OUT16_6") (pintype "output"))
      (node (ref "TUBE2") (pin "20") (pinfunction "20_20") (pintype "bidirectional"))
    )
    (net (code "59") (name "Net-(SHIFT2-OUT17)") (class "Default")
      (node (ref "SHIFT2") (pin "5") (pinfunction "OUT17_5") (pintype "output"))
      (node (ref "TUBE2") (pin "21") (pinfunction "21_21") (pintype "bidirectional"))
    )
    (net (code "60") (name "Net-(SHIFT3-DOUT)") (class "Default")
      (node (ref "SHIFT3") (pin "2") (pinfunction "DOUT_2") (pintype "output"))
      (node (ref "SHIFT4") (pin "27") (pinfunction "DIN_27") (pintype "input"))
    )
    (net (code "61") (name "Net-(SHIFT3-OUT0)") (class "Default")
      (node (ref "SHIFT3") (pin "26") (pinfunction "OUT0_26") (pintype "output"))
      (node (ref "TUBE3") (pin "2") (pinfunction "2_2") (pintype "bidirectional"))
    )
    (net (code "62") (name "Net-(SHIFT3-OUT1)") (class "Default")
      (node (ref "SHIFT3") (pin "25") (pinfunction "OUT1_25") (pintype "output"))
      (node (ref "TUBE3") (pin "3") (pinfunction "3_3") (pintype "bidirectional"))
    )
    (net (code "63") (name "Net-(SHIFT3-OUT2)") (class "Default")
      (node (ref "SHIFT3") (pin "24") (pinfunction "OUT2_24") (pintype "output"))
      (node (ref "TUBE3") (pin "4") (pinfunction "4_4") (pintype "bidirectional"))
    )
    (net (code "64") (name "Net-(SHIFT3-OUT3)") (class "Default")
      (node (ref "SHIFT3") (pin "23") (pinfunction "OUT3_23") (pintype "output"))
      (node (ref "TUBE3") (pin "5") (pinfunction "5_5") (pintype "bidirectional"))
    )
    (net (code "65") (name "Net-(SHIFT3-OUT4)") (class "Default")
      (node (ref "SHIFT3") (pin "22") (pinfunction "OUT4_22") (pintype "output"))
      (node (ref "TUBE3") (pin "6") (pinfunction "6_6") (pintype "bidirectional"))
    )
    (net (code "66") (name "Net-(SHIFT3-OUT5)") (class "Default")
      (node (ref "SHIFT3") (pin "21") (pinfunction "OUT5_21") (pintype "output"))
      (node (ref "TUBE3") (pin "7") (pinfunction "7_7") (pintype "bidirectional"))
    )
    (net (code "67") (name "Net-(SHIFT3-OUT6)") (class "Default")
      (node (ref "SHIFT3") (pin "20") (pinfunction "OUT6_20") (pintype "output"))
      (node (ref "TUBE3") (pin "8") (pinfunction "8_8") (pintype "bidirectional"))
    )
    (net (code "68") (name "Net-(SHIFT3-OUT7)") (class "Default")
      (node (ref "SHIFT3") (pin "19") (pinfunction "OUT7_19") (pintype "output"))
      (node (ref "TUBE3") (pin "9") (pinfunction "9_9") (pintype "bidirectional"))
    )
    (net (code "69") (name "Net-(SHIFT3-OUT8)") (class "Default")
      (node (ref "SHIFT3") (pin "18") (pinfunction "OUT8_18") (pintype "output"))
      (node (ref "TUBE3") (pin "10") (pinfunction "10_10") (pintype "bidirectional"))
    )
    (net (code "70") (name "Net-(SHIFT3-OUT9)") (class "Default")
      (node (ref "SHIFT3") (pin "17") (pinfunction "OUT9_17") (pintype "output"))
      (node (ref "TUBE3") (pin "13") (pinfunction "13_13") (pintype "bidirectional"))
    )
    (net (code "71") (name "Net-(SHIFT3-OUT10)") (class "Default")
      (node (ref "SHIFT3") (pin "12") (pinfunction "OUT10_12") (pintype "output"))
      (node (ref "TUBE3") (pin "14") (pinfunction "14_14") (pintype "bidirectional"))
    )
    (net (code "72") (name "Net-(SHIFT3-OUT11)") (class "Default")
      (node (ref "SHIFT3") (pin "11") (pinfunction "OUT11_11") (pintype "output"))
      (node (ref "TUBE3") (pin "15") (pinfunction "15_15") (pintype "bidirectional"))
    )
    (net (code "73") (name "Net-(SHIFT3-OUT12)") (class "Default")
      (node (ref "SHIFT3") (pin "10") (pinfunction "OUT12_10") (pintype "output"))
      (node (ref "TUBE3") (pin "16") (pinfunction "16_16") (pintype "bidirectional"))
    )
    (net (code "74") (name "Net-(SHIFT3-OUT13)") (class "Default")
      (node (ref "SHIFT3") (pin "9") (pinfunction "OUT13_9") (pintype "output"))
      (node (ref "TUBE3") (pin "17") (pinfunction "17_17") (pintype "bidirectional"))
    )
    (net (code "75") (name "Net-(SHIFT3-OUT14)") (class "Default")
      (node (ref "SHIFT3") (pin "8") (pinfunction "OUT14_8") (pintype "output"))
      (node (ref "TUBE3") (pin "18") (pinfunction "18_18") (pintype "bidirectional"))
    )
    (net (code "76") (name "Net-(SHIFT3-OUT15)") (class "Default")
      (node (ref "SHIFT3") (pin "7") (pinfunction "OUT15_7") (pintype "output"))
      (node (ref "TUBE3") (pin "19") (pinfunction "19_19") (pintype "bidirectional"))
    )
    (net (code "77") (name "Net-(SHIFT3-OUT16)") (class "Default")
      (node (ref "SHIFT3") (pin "6") (pinfunction "OUT16_6") (pintype "output"))
      (node (ref "TUBE3") (pin "20") (pinfunction "20_20") (pintype "bidirectional"))
    )
    (net (code "78") (name "Net-(SHIFT3-OUT17)") (class "Default")
      (node (ref "SHIFT3") (pin "5") (pinfunction "OUT17_5") (pintype "output"))
      (node (ref "TUBE3") (pin "21") (pinfunction "21_21") (pintype "bidirectional"))
    )
    (net (code "79") (name "Net-(SHIFT4-DOUT)") (class "Default")
      (node (ref "SHIFT4") (pin "2") (pinfunction "DOUT_2") (pintype "output"))
      (node (ref "SHIFT5") (pin "27") (pinfunction "DIN_27") (pintype "input"))
    )
    (net (code "80") (name "Net-(SHIFT4-OUT0)") (class "Default")
      (node (ref "SHIFT4") (pin "26") (pinfunction "OUT0_26") (pintype "output"))
      (node (ref "TUBE4") (pin "2") (pinfunction "2_2") (pintype "bidirectional"))
    )
    (net (code "81") (name "Net-(SHIFT4-OUT1)") (class "Default")
      (node (ref "SHIFT4") (pin "25") (pinfunction "OUT1_25") (pintype "output"))
      (node (ref "TUBE4") (pin "3") (pinfunction "3_3") (pintype "bidirectional"))
    )
    (net (code "82") (name "Net-(SHIFT4-OUT2)") (class "Default")
      (node (ref "SHIFT4") (pin "24") (pinfunction "OUT2_24") (pintype "output"))
      (node (ref "TUBE4") (pin "4") (pinfunction "4_4") (pintype "bidirectional"))
    )
    (net (code "83") (name "Net-(SHIFT4-OUT3)") (class "Default")
      (node (ref "SHIFT4") (pin "23") (pinfunction "OUT3_23") (pintype "output"))
      (node (ref "TUBE4") (pin "5") (pinfunction "5_5") (pintype "bidirectional"))
    )
    (net (code "84") (name "Net-(SHIFT4-OUT4)") (class "Default")
      (node (ref "SHIFT4") (pin "22") (pinfunction "OUT4_22") (pintype "output"))
      (node (ref "TUBE4") (pin "6") (pinfunction "6_6") (pintype "bidirectional"))
    )
    (net (code "85") (name "Net-(SHIFT4-OUT5)") (class "Default")
      (node (ref "SHIFT4") (pin "21") (pinfunction "OUT5_21") (pintype "output"))
      (node (ref "TUBE4") (pin "7") (pinfunction "7_7") (pintype "bidirectional"))
    )
    (net (code "86") (name "Net-(SHIFT4-OUT6)") (class "Default")
      (node (ref "SHIFT4") (pin "20") (pinfunction "OUT6_20") (pintype "output"))
      (node (ref "TUBE4") (pin "8") (pinfunction "8_8") (pintype "bidirectional"))
    )
    (net (code "87") (name "Net-(SHIFT4-OUT7)") (class "Default")
      (node (ref "SHIFT4") (pin "19") (pinfunction "OUT7_19") (pintype "output"))
      (node (ref "TUBE4") (pin "9") (pinfunction "9_9") (pintype "bidirectional"))
    )
    (net (code "88") (name "Net-(SHIFT4-OUT8)") (class "Default")
      (node (ref "SHIFT4") (pin "18") (pinfunction "OUT8_18") (pintype "output"))
      (node (ref "TUBE4") (pin "10") (pinfunction "10_10") (pintype "bidirectional"))
    )
    (net (code "89") (name "Net-(SHIFT4-OUT9)") (class "Default")
      (node (ref "SHIFT4") (pin "17") (pinfunction "OUT9_17") (pintype "output"))
      (node (ref "TUBE4") (pin "13") (pinfunction "13_13") (pintype "bidirectional"))
    )
    (net (code "90") (name "Net-(SHIFT4-OUT10)") (class "Default")
      (node (ref "SHIFT4") (pin "12") (pinfunction "OUT10_12") (pintype "output"))
      (node (ref "TUBE4") (pin "14") (pinfunction "14_14") (pintype "bidirectional"))
    )
    (net (code "91") (name "Net-(SHIFT4-OUT11)") (class "Default")
      (node (ref "SHIFT4") (pin "11") (pinfunction "OUT11_11") (pintype "output"))
      (node (ref "TUBE4") (pin "15") (pinfunction "15_15") (pintype "bidirectional"))
    )
    (net (code "92") (name "Net-(SHIFT4-OUT12)") (class "Default")
      (node (ref "SHIFT4") (pin "10") (pinfunction "OUT12_10") (pintype "output"))
      (node (ref "TUBE4") (pin "16") (pinfunction "16_16") (pintype "bidirectional"))
    )
    (net (code "93") (name "Net-(SHIFT4-OUT13)") (class "Default")
      (node (ref "SHIFT4") (pin "9") (pinfunction "OUT13_9") (pintype "output"))
      (node (ref "TUBE4") (pin "17") (pinfunction "17_17") (pintype "bidirectional"))
    )
    (net (code "94") (name "Net-(SHIFT4-OUT14)") (class "Default")
      (node (ref "SHIFT4") (pin "8") (pinfunction "OUT14_8") (pintype "output"))
      (node (ref "TUBE4") (pin "18") (pinfunction "18_18") (pintype "bidirectional"))
    )
    (net (code "95") (name "Net-(SHIFT4-OUT15)") (class "Default")
      (node (ref "SHIFT4") (pin "7") (pinfunction "OUT15_7") (pintype "output"))
      (node (ref "TUBE4") (pin "19") (pinfunction "19_19") (pintype "bidirectional"))
    )
    (net (code "96") (name "Net-(SHIFT4-OUT16)") (class "Default")
      (node (ref "SHIFT4") (pin "6") (pinfunction "OUT16_6") (pintype "output"))
      (node (ref "TUBE4") (pin "20") (pinfunction "20_20") (pintype "bidirectional"))
    )
    (net (code "97") (name "Net-(SHIFT4-OUT17)") (class "Default")
      (node (ref "SHIFT4") (pin "5") (pinfunction "OUT17_5") (pintype "output"))
      (node (ref "TUBE4") (pin "21") (pinfunction "21_21") (pintype "bidirectional"))
    )
    (net (code "98") (name "Net-(SHIFT5-DOUT)") (class "Default")
      (node (ref "SHIFT5") (pin "2") (pinfunction "DOUT_2") (pintype "output"))
      (node (ref "SHIFT6") (pin "27") (pinfunction "DIN_27") (pintype "input"))
    )
    (net (code "99") (name "Net-(SHIFT5-OUT0)") (class "Default")
      (node (ref "SHIFT5") (pin "26") (pinfunction "OUT0_26") (pintype "output"))
      (node (ref "TUBE5") (pin "2") (pinfunction "2_2") (pintype "bidirectional"))
    )
    (net (code "100") (name "Net-(SHIFT5-OUT1)") (class "Default")
      (node (ref "SHIFT5") (pin "25") (pinfunction "OUT1_25") (pintype "output"))
      (node (ref "TUBE5") (pin "3") (pinfunction "3_3") (pintype "bidirectional"))
    )
    (net (code "101") (name "Net-(SHIFT5-OUT2)") (class "Default")
      (node (ref "SHIFT5") (pin "24") (pinfunction "OUT2_24") (pintype "output"))
      (node (ref "TUBE5") (pin "4") (pinfunction "4_4") (pintype "bidirectional"))
    )
    (net (code "102") (name "Net-(SHIFT5-OUT3)") (class "Default")
      (node (ref "SHIFT5") (pin "23") (pinfunction "OUT3_23") (pintype "output"))
      (node (ref "TUBE5") (pin "5") (pinfunction "5_5") (pintype "bidirectional"))
    )
    (net (code "103") (name "Net-(SHIFT5-OUT4)") (class "Default")
      (node (ref "SHIFT5") (pin "22") (pinfunction "OUT4_22") (pintype "output"))
      (node (ref "TUBE5") (pin "6") (pinfunction "6_6") (pintype "bidirectional"))
    )
    (net (code "104") (name "Net-(SHIFT5-OUT5)") (class "Default")
      (node (ref "SHIFT5") (pin "21") (pinfunction "OUT5_21") (pintype "output"))
      (node (ref "TUBE5") (pin "7") (pinfunction "7_7") (pintype "bidirectional"))
    )
    (net (code "105") (name "Net-(SHIFT5-OUT6)") (class "Default")
      (node (ref "SHIFT5") (pin "20") (pinfunction "OUT6_20") (pintype "output"))
      (node (ref "TUBE5") (pin "8") (pinfunction "8_8") (pintype "bidirectional"))
    )
    (net (code "106") (name "Net-(SHIFT5-OUT7)") (class "Default")
      (node (ref "SHIFT5") (pin "19") (pinfunction "OUT7_19") (pintype "output"))
      (node (ref "TUBE5") (pin "9") (pinfunction "9_9") (pintype "bidirectional"))
    )
    (net (code "107") (name "Net-(SHIFT5-OUT8)") (class "Default")
      (node (ref "SHIFT5") (pin "18") (pinfunction "OUT8_18") (pintype "output"))
      (node (ref "TUBE5") (pin "10") (pinfunction "10_10") (pintype "bidirectional"))
    )
    (net (code "108") (name "Net-(SHIFT5-OUT9)") (class "Default")
      (node (ref "SHIFT5") (pin "17") (pinfunction "OUT9_17") (pintype "output"))
      (node (ref "TUBE5") (pin "13") (pinfunction "13_13") (pintype "bidirectional"))
    )
    (net (code "109") (name "Net-(SHIFT5-OUT10)") (class "Default")
      (node (ref "SHIFT5") (pin "12") (pinfunction "OUT10_12") (pintype "output"))
      (node (ref "TUBE5") (pin "14") (pinfunction "14_14") (pintype "bidirectional"))
    )
    (net (code "110") (name "Net-(SHIFT5-OUT11)") (class "Default")
      (node (ref "SHIFT5") (pin "11") (pinfunction "OUT11_11") (pintype "output"))
      (node (ref "TUBE5") (pin "15") (pinfunction "15_15") (pintype "bidirectional"))
    )
    (net (code "111") (name "Net-(SHIFT5-OUT12)") (class "Default")
      (node (ref "SHIFT5") (pin "10") (pinfunction "OUT12_10") (pintype "output"))
      (node (ref "TUBE5") (pin "16") (pinfunction "16_16") (pintype "bidirectional"))
    )
    (net (code "112") (name "Net-(SHIFT5-OUT13)") (class "Default")
      (node (ref "SHIFT5") (pin "9") (pinfunction "OUT13_9") (pintype "output"))
      (node (ref "TUBE5") (pin "17") (pinfunction "17_17") (pintype "bidirectional"))
    )
    (net (code "113") (name "Net-(SHIFT5-OUT14)") (class "Default")
      (node (ref "SHIFT5") (pin "8") (pinfunction "OUT14_8") (pintype "output"))
      (node (ref "TUBE5") (pin "18") (pinfunction "18_18") (pintype "bidirectional"))
    )
    (net (code "114") (name "Net-(SHIFT5-OUT15)") (class "Default")
      (node (ref "SHIFT5") (pin "7") (pinfunction "OUT15_7") (pintype "output"))
      (node (ref "TUBE5") (pin "19") (pinfunction "19_19") (pintype "bidirectional"))
    )
    (net (code "115") (name "Net-(SHIFT5-OUT16)") (class "Default")
      (node (ref "SHIFT5") (pin "6") (pinfunction "OUT16_6") (pintype "output"))
      (node (ref "TUBE5") (pin "20") (pinfunction "20_20") (pintype "bidirectional"))
    )
    (net (code "116") (name "Net-(SHIFT5-OUT17)") (class "Default")
      (node (ref "SHIFT5") (pin "5") (pinfunction "OUT17_5") (pintype "output"))
      (node (ref "TUBE5") (pin "21") (pinfunction "21_21") (pintype "bidirectional"))
    )
    (net (code "117") (name "Net-(SHIFT6-OUT0)") (class "Default")
      (node (ref "SHIFT6") (pin "26") (pinfunction "OUT0_26") (pintype "output"))
      (node (ref "TUBE6") (pin "2") (pinfunction "2_2") (pintype "bidirectional"))
    )
    (net (code "118") (name "Net-(SHIFT6-OUT1)") (class "Default")
      (node (ref "SHIFT6") (pin "25") (pinfunction "OUT1_25") (pintype "output"))
      (node (ref "TUBE6") (pin "3") (pinfunction "3_3") (pintype "bidirectional"))
    )
    (net (code "119") (name "Net-(SHIFT6-OUT2)") (class "Default")
      (node (ref "SHIFT6") (pin "24") (pinfunction "OUT2_24") (pintype "output"))
      (node (ref "TUBE6") (pin "4") (pinfunction "4_4") (pintype "bidirectional"))
    )
    (net (code "120") (name "Net-(SHIFT6-OUT3)") (class "Default")
      (node (ref "SHIFT6") (pin "23") (pinfunction "OUT3_23") (pintype "output"))
      (node (ref "TUBE6") (pin "5") (pinfunction "5_5") (pintype "bidirectional"))
    )
    (net (code "121") (name "Net-(SHIFT6-OUT4)") (class "Default")
      (node (ref "SHIFT6") (pin "22") (pinfunction "OUT4_22") (pintype "output"))
      (node (ref "TUBE6") (pin "6") (pinfunction "6_6") (pintype "bidirectional"))
    )
    (net (code "122") (name "Net-(SHIFT6-OUT5)") (class "Default")
      (node (ref "SHIFT6") (pin "21") (pinfunction "OUT5_21") (pintype "output"))
      (node (ref "TUBE6") (pin "7") (pinfunction "7_7") (pintype "bidirectional"))
    )
    (net (code "123") (name "Net-(SHIFT6-OUT6)") (class "Default")
      (node (ref "SHIFT6") (pin "20") (pinfunction "OUT6_20") (pintype "output"))
      (node (ref "TUBE6") (pin "8") (pinfunction "8_8") (pintype "bidirectional"))
    )
    (net (code "124") (name "Net-(SHIFT6-OUT7)") (class "Default")
      (node (ref "SHIFT6") (pin "19") (pinfunction "OUT7_19") (pintype "output"))
      (node (ref "TUBE6") (pin "9") (pinfunction "9_9") (pintype "bidirectional"))
    )
    (net (code "125") (name "Net-(SHIFT6-OUT8)") (class "Default")
      (node (ref "SHIFT6") (pin "18") (pinfunction "OUT8_18") (pintype "output"))
      (node (ref "TUBE6") (pin "10") (pinfunction "10_10") (pintype "bidirectional"))
    )
    (net (code "126") (name "Net-(SHIFT6-OUT9)") (class "Default")
      (node (ref "SHIFT6") (pin "17") (pinfunction "OUT9_17") (pintype "output"))
      (node (ref "TUBE6") (pin "13") (pinfunction "13_13") (pintype "bidirectional"))
    )
    (net (code "127") (name "Net-(SHIFT6-OUT10)") (class "Default")
      (node (ref "SHIFT6") (pin "12") (pinfunction "OUT10_12") (pintype "output"))
      (node (ref "TUBE6") (pin "14") (pinfunction "14_14") (pintype "bidirectional"))
    )
    (net (code "128") (name "Net-(SHIFT6-OUT11)") (class "Default")
      (node (ref "SHIFT6") (pin "11") (pinfunction "OUT11_11") (pintype "output"))
      (node (ref "TUBE6") (pin "15") (pinfunction "15_15") (pintype "bidirectional"))
    )
    (net (code "129") (name "Net-(SHIFT6-OUT12)") (class "Default")
      (node (ref "SHIFT6") (pin "10") (pinfunction "OUT12_10") (pintype "output"))
      (node (ref "TUBE6") (pin "16") (pinfunction "16_16") (pintype "bidirectional"))
    )
    (net (code "130") (name "Net-(SHIFT6-OUT13)") (class "Default")
      (node (ref "SHIFT6") (pin "9") (pinfunction "OUT13_9") (pintype "output"))
      (node (ref "TUBE6") (pin "17") (pinfunction "17_17") (pintype "bidirectional"))
    )
    (net (code "131") (name "Net-(SHIFT6-OUT14)") (class "Default")
      (node (ref "SHIFT6") (pin "8") (pinfunction "OUT14_8") (pintype "output"))
      (node (ref "TUBE6") (pin "18") (pinfunction "18_18") (pintype "bidirectional"))
    )
    (net (code "132") (name "Net-(SHIFT6-OUT15)") (class "Default")
      (node (ref "SHIFT6") (pin "7") (pinfunction "OUT15_7") (pintype "output"))
      (node (ref "TUBE6") (pin "19") (pinfunction "19_19") (pintype "bidirectional"))
    )
    (net (code "133") (name "Net-(SHIFT6-OUT16)") (class "Default")
      (node (ref "SHIFT6") (pin "6") (pinfunction "OUT16_6") (pintype "output"))
      (node (ref "TUBE6") (pin "20") (pinfunction "20_20") (pintype "bidirectional"))
    )
    (net (code "134") (name "Net-(SHIFT6-OUT17)") (class "Default")
      (node (ref "SHIFT6") (pin "5") (pinfunction "OUT17_5") (pintype "output"))
      (node (ref "TUBE6") (pin "21") (pinfunction "21_21") (pintype "bidirectional"))
    )
    (net (code "135") (name "Net-(TUBE1-11FIL-)") (class "Default")
      (node (ref "TUBE1") (pin "11") (pinfunction "11FIL-_11") (pintype "bidirectional"))
      (node (ref "TUBE2") (pin "1") (pinfunction "1FIL+_1") (pintype "bidirectional"))
    )
    (net (code "136") (name "Net-(TUBE2-11FIL-)") (class "Default")
      (node (ref "R3") (pin "2") (pinfunction "2_2") (pintype "passive"))
      (node (ref "TUBE2") (pin "11") (pinfunction "11FIL-_11") (pintype "bidirectional"))
      (node (ref "TUBE4") (pin "11") (pinfunction "11FIL-_11") (pintype "bidirectional"))
      (node (ref "TUBE6") (pin "11") (pinfunction "11FIL-_11") (pintype "bidirectional"))
    )
    (net (code "137") (name "Net-(TUBE3-11FIL-)") (class "Default")
      (node (ref "TUBE3") (pin "11") (pinfunction "11FIL-_11") (pintype "bidirectional"))
      (node (ref "TUBE4") (pin "1") (pinfunction "1FIL+_1") (pintype "bidirectional"))
    )
    (net (code "138") (name "Net-(TUBE5-11FIL-)") (class "Default")
      (node (ref "TUBE5") (pin "11") (pinfunction "11FIL-_11") (pintype "bidirectional"))
      (node (ref "TUBE6") (pin "1") (pinfunction "1FIL+_1") (pintype "bidirectional"))
    )
    (net (code "139") (name "Net-(U1-PB6(XTAL1{slash}TOSC1))") (class "Default")
      (node (ref "C5") (pin "1") (pinfunction "1_1") (pintype "passive"))
      (node (ref "Q1") (pin "2") (pinfunction "2_2") (pintype "passive"))
      (node (ref "U1") (pin "9") (pinfunction "PB6(XTAL1/TOSC1)_9") (pintype "bidirectional"))
    )
    (net (code "140") (name "Net-(U1-PB7(XTAL2{slash}TOSC2))") (class "Default")
      (node (ref "C6") (pin "1") (pinfunction "1_1") (pintype "passive"))
      (node (ref "Q1") (pin "1") (pinfunction "1_1") (pintype "passive"))
      (node (ref "U1") (pin "10") (pinfunction "PB7(XTAL2/TOSC2)_10") (pintype "bidirectional"))
    )
    (net (code "141") (name "PB0") (class "Default")
      (node (ref "JPB") (pin "2") (pinfunction "2_2") (pintype "passive"))
      (node (ref "R2") (pin "2") (pinfunction "2_2") (pintype "passive"))
      (node (ref "U1") (pin "14") (pinfunction "PB0(ICP)_14") (pintype "bidirectional"))
    )
    (net (code "142") (name "PB2") (class "Default")
      (node (ref "JPB") (pin "4") (pinfunction "4_4") (pintype "passive"))
      (node (ref "U1") (pin "16") (pinfunction "PB2(SS/OC1B)_16") (pintype "bidirectional"))
    )
    (net (code "143") (name "PB3") (class "Default")
      (node (ref "JPB") (pin "5") (pinfunction "5_5") (pintype "passive"))
      (node (ref "U1") (pin "17") (pinfunction "PB3(MOSI/OC2)_17") (pintype "bidirectional"))
    )
    (net (code "144") (name "PB4") (class "Default")
      (node (ref "JPB") (pin "6") (pinfunction "6_6") (pintype "passive"))
      (node (ref "U1") (pin "18") (pinfunction "PB4(MISO)_18") (pintype "bidirectional"))
    )
    (net (code "145") (name "PB5") (class "Default")
      (node (ref "JPB") (pin "7") (pinfunction "7_7") (pintype "passive"))
      (node (ref "U1") (pin "19") (pinfunction "PB5(SCK)_19") (pintype "bidirectional"))
    )
    (net (code "146") (name "PC4") (class "Default")
      (node (ref "JPA") (pin "2") (pinfunction "2_2") (pintype "passive"))
      (node (ref "U1") (pin "27") (pinfunction "PC4(ADC4/SDA)_27") (pintype "bidirectional"))
    )
    (net (code "147") (name "PC5") (class "Default")
      (node (ref "JPA") (pin "7") (pinfunction "7_7") (pintype "passive"))
      (node (ref "U1") (pin "28") (pinfunction "PC5(ADC5/SCL)_28") (pintype "bidirectional"))
    )
    (net (code "148") (name "PD3") (class "Default")
      (node (ref "JPD") (pin "2") (pinfunction "2_2") (pintype "passive"))
      (node (ref "U1") (pin "5") (pinfunction "PD3(INT1)_5") (pintype "bidirectional"))
    )
    (net (code "149") (name "PD4") (class "Default")
      (node (ref "JPD") (pin "3") (pinfunction "3_3") (pintype "passive"))
      (node (ref "U1") (pin "6") (pinfunction "PD4(XCK/T0)_6") (pintype "bidirectional"))
    )
    (net (code "150") (name "PD5") (class "Default")
      (node (ref "JPD") (pin "4") (pinfunction "4_4") (pintype "passive"))
      (node (ref "U1") (pin "11") (pinfunction "PD5(T1)_11") (pintype "bidirectional"))
    )
    (net (code "151") (name "PD6") (class "Default")
      (node (ref "JPD") (pin "5") (pinfunction "5_5") (pintype "passive"))
      (node (ref "U1") (pin "12") (pinfunction "PD6(AIN0)_12") (pintype "bidirectional"))
    )
    (net (code "152") (name "PD7") (class "Default")
      (node (ref "JPD") (pin "6") (pinfunction "6_6") (pintype "passive"))
      (node (ref "U1") (pin "13") (pinfunction "PD7(AIN1)_13") (pintype "bidirectional"))
    )
    (net (code "153") (name "VCC") (class "Default")
      (node (ref "C3") (pin "1") (pinfunction "1_1") (pintype "passive"))
      (node (ref "C4") (pin "1") (pinfunction "1_1") (pintype "passive"))
      (node (ref "C8") (pin "+") (pinfunction "+_+") (pintype "passive"))
      (node (ref "IC1") (pin "3") (pinfunction "VO_3") (pintype "passive"))
      (node (ref "JPA") (pin "1") (pinfunction "1_1") (pintype "passive"))
      (node (ref "JPA") (pin "6") (pinfunction "6_6") (pintype "passive"))
      (node (ref "JPB") (pin "1") (pinfunction "1_1") (pintype "passive"))
      (node (ref "JPD") (pin "1") (pinfunction "1_1") (pintype "passive"))
      (node (ref "R1") (pin "2") (pinfunction "2_2") (pintype "passive"))
      (node (ref "R4") (pin "2") (pinfunction "2_2") (pintype "passive"))
      (node (ref "U1") (pin "20") (pinfunction "AVCC_20") (pintype "bidirectional"))
      (node (ref "U1") (pin "7") (pinfunction "VCC_7") (pintype "bidirectional"))
    )
    (net (code "154") (name "VFIL") (class "Default")
      (node (ref "C7") (pin "+") (pinfunction "+_+") (pintype "passive"))
      (node (ref "IC2") (pin "3") (pinfunction "VO_3") (pintype "passive"))
      (node (ref "R5") (pin "2") (pinfunction "2_2") (pintype "passive"))
      (node (ref "TUBE1") (pin "1") (pinfunction "1FIL+_1") (pintype "bidirectional"))
      (node (ref "TUBE3") (pin "1") (pinfunction "1FIL+_1") (pintype "bidirectional"))
      (node (ref "TUBE5") (pin "1") (pinfunction "1FIL+_1") (pintype "bidirectional"))
    )
    (net (code "155") (name "unconnected-(JPA-Pad4)") (class "Default")
      (node (ref "JPA") (pin "4") (pinfunction "4_4") (pintype "passive"))
    )
    (net (code "156") (name "unconnected-(JPA-Pad5)") (class "Default")
      (node (ref "JPA") (pin "5") (pinfunction "5_5") (pintype "passive"))
    )
    (net (code "157") (name "unconnected-(JPB-Pad3)") (class "Default")
      (node (ref "JPB") (pin "3") (pinfunction "3_3") (pintype "passive"))
    )
    (net (code "158") (name "unconnected-(JPD-Pad7)") (class "Default")
      (node (ref "JPD") (pin "7") (pinfunction "7_7") (pintype "passive"))
    )
    (net (code "159") (name "unconnected-(L6-DOUT-Pad2-DOUT)") (class "Default")
      (node (ref "L6") (pin "2-DOUT") (pinfunction "DOUT_2-DOUT") (pintype "output"))
    )
    (net (code "160") (name "unconnected-(SHIFT1-OUT18-Pad4)") (class "Default")
      (node (ref "SHIFT1") (pin "4") (pinfunction "OUT18_4") (pintype "output"))
    )
    (net (code "161") (name "unconnected-(SHIFT1-OUT19-Pad3)") (class "Default")
      (node (ref "SHIFT1") (pin "3") (pinfunction "OUT19_3") (pintype "output"))
    )
    (net (code "162") (name "unconnected-(SHIFT2-OUT18-Pad4)") (class "Default")
      (node (ref "SHIFT2") (pin "4") (pinfunction "OUT18_4") (pintype "output"))
    )
    (net (code "163") (name "unconnected-(SHIFT2-OUT19-Pad3)") (class "Default")
      (node (ref "SHIFT2") (pin "3") (pinfunction "OUT19_3") (pintype "output"))
    )
    (net (code "164") (name "unconnected-(SHIFT3-OUT18-Pad4)") (class "Default")
      (node (ref "SHIFT3") (pin "4") (pinfunction "OUT18_4") (pintype "output"))
    )
    (net (code "165") (name "unconnected-(SHIFT3-OUT19-Pad3)") (class "Default")
      (node (ref "SHIFT3") (pin "3") (pinfunction "OUT19_3") (pintype "output"))
    )
    (net (code "166") (name "unconnected-(SHIFT4-OUT18-Pad4)") (class "Default")
      (node (ref "SHIFT4") (pin "4") (pinfunction "OUT18_4") (pintype "output"))
    )
    (net (code "167") (name "unconnected-(SHIFT4-OUT19-Pad3)") (class "Default")
      (node (ref "SHIFT4") (pin "3") (pinfunction "OUT19_3") (pintype "output"))
    )
    (net (code "168") (name "unconnected-(SHIFT5-OUT18-Pad4)") (class "Default")
      (node (ref "SHIFT5") (pin "4") (pinfunction "OUT18_4") (pintype "output"))
    )
    (net (code "169") (name "unconnected-(SHIFT5-OUT19-Pad3)") (class "Default")
      (node (ref "SHIFT5") (pin "3") (pinfunction "OUT19_3") (pintype "output"))
    )
    (net (code "170") (name "unconnected-(SHIFT6-DOUT-Pad2)") (class "Default")
      (node (ref "SHIFT6") (pin "2") (pinfunction "DOUT_2") (pintype "output"))
    )
    (net (code "171") (name "unconnected-(SHIFT6-OUT18-Pad4)") (class "Default")
      (node (ref "SHIFT6") (pin "4") (pinfunction "OUT18_4") (pintype "output"))
    )
    (net (code "172") (name "unconnected-(SHIFT6-OUT19-Pad3)") (class "Default")
      (node (ref "SHIFT6") (pin "3") (pinfunction "OUT19_3") (pintype "output"))
    )
    (net (code "173") (name "unconnected-(U1-AREF-Pad21)") (class "Default")
      (node (ref "U1") (pin "21") (pinfunction "AREF_21") (pintype "bidirectional"))
    )
    (net (code "174") (name "unconnected-(X1--1-PadA1)") (class "Default")
      (node (ref "X1") (pin "A1") (pinfunction "-1_A1") (pintype "passive"))
    )
    (net (code "175") (name "unconnected-(X1--2-PadA2)") (class "Default")
      (node (ref "X1") (pin "A2") (pinfunction "-2_A2") (pintype "passive"))
    )
  )
)
